# fullCURRENT_control.net
KiCad netlist of a schematic drawn in Altium Designer
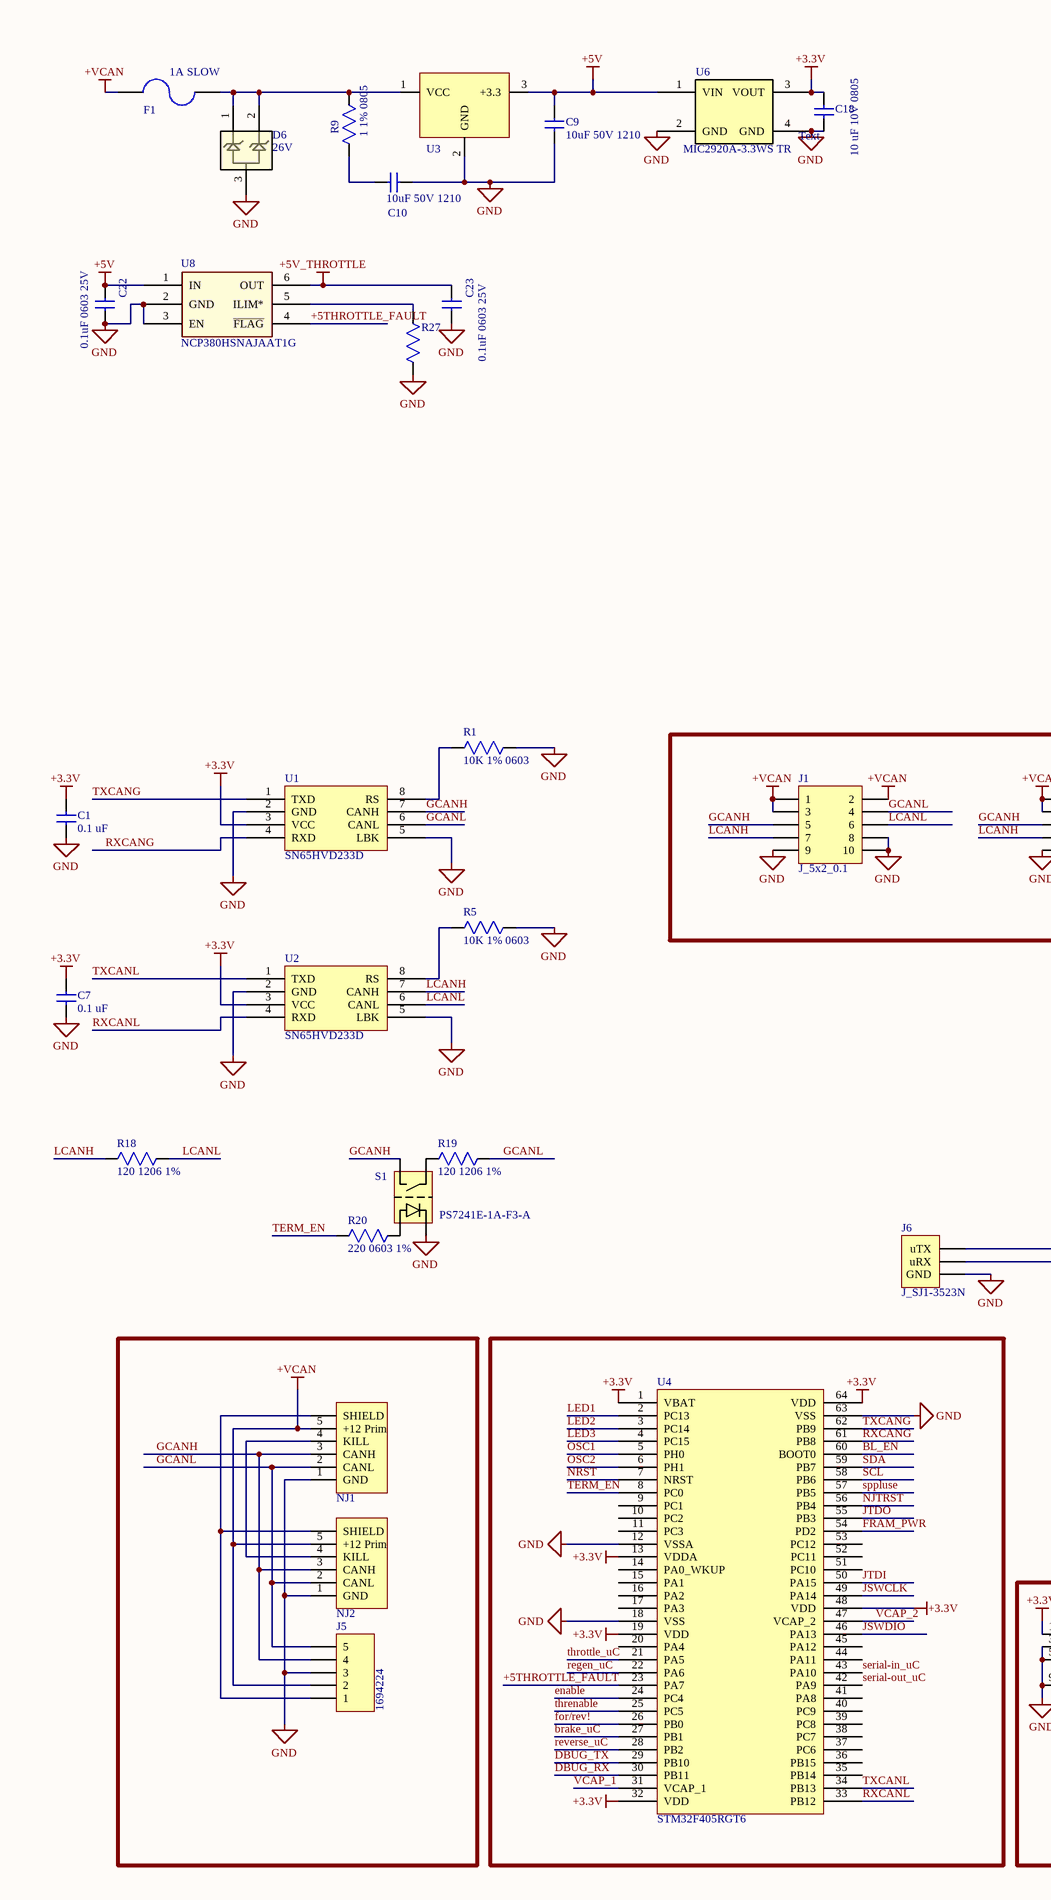
[diagram p0: fullCURRENT control.SchDoc, left]
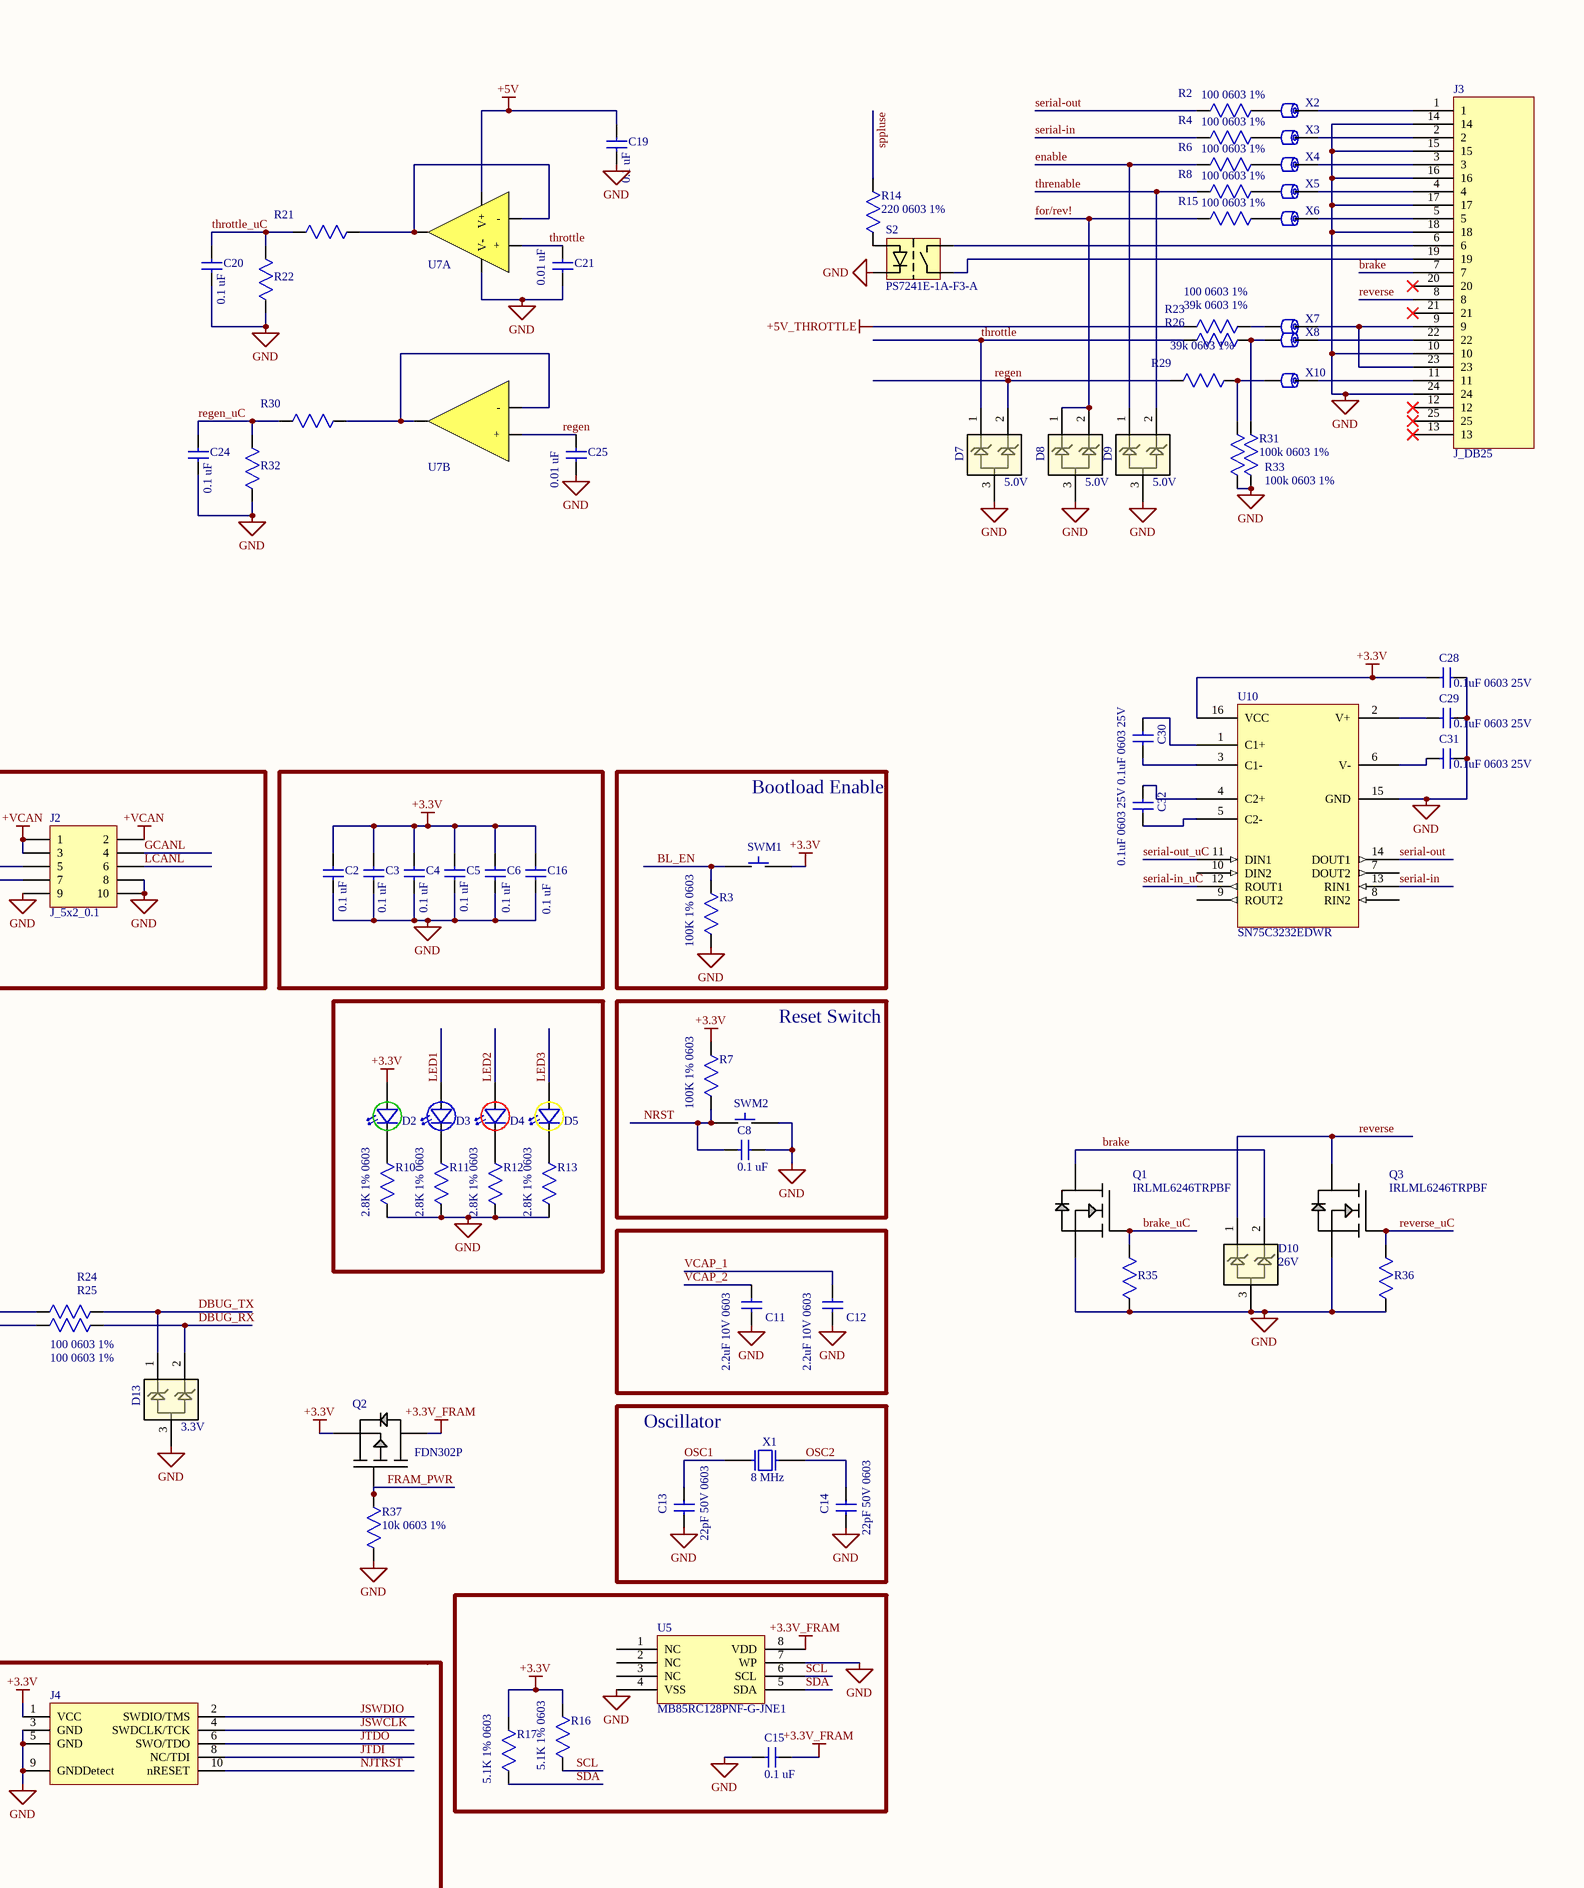
[diagram p1: fullCURRENT control.SchDoc, right]

(export (version "E")
  (design (tool "Eeschema 10.0.6"))
  (components
    (comp (ref "C1")
      (value "0.1 uF")
      (footprint "0603_cap")
      (description "CAP CERM 0.1uF 0603 X7R")
      (fields (field (name "MANUFACTURER") "Murata") (field (name "PART NUMBER") "GRM188R71E104KA01D"))
      (libsource (lib "Nutz") (part "C_0603"))
    )
    (comp (ref "C2")
      (value "0.1 uF")
      (footprint "0603_cap")
      (description "CAP CERM 0.1uF 0603 X7R")
      (fields (field (name "MANUFACTURER") "Murata") (field (name "PART NUMBER") "GRM188R71E104KA01D"))
      (libsource (lib "Nutz") (part "C_0603"))
    )
    (comp (ref "C3")
      (value "0.1 uF")
      (footprint "0603_cap")
      (description "CAP CERM 0.1uF 0603 X7R")
      (fields (field (name "MANUFACTURER") "Murata") (field (name "PART NUMBER") "GRM188R71E104KA01D"))
      (libsource (lib "Nutz") (part "C_0603"))
    )
    (comp (ref "C4")
      (value "0.1 uF")
      (footprint "0603_cap")
      (description "CAP CERM 0.1uF 0603 X7R")
      (fields (field (name "MANUFACTURER") "Murata") (field (name "PART NUMBER") "GRM188R71E104KA01D"))
      (libsource (lib "Nutz") (part "C_0603"))
    )
    (comp (ref "C5")
      (value "0.1 uF")
      (footprint "0603_cap")
      (description "CAP CERM 0.1uF 0603 X7R")
      (fields (field (name "MANUFACTURER") "Murata") (field (name "PART NUMBER") "GRM188R71E104KA01D"))
      (libsource (lib "Nutz") (part "C_0603"))
    )
    (comp (ref "C6")
      (value "0.1 uF")
      (footprint "0603_cap")
      (description "CAP CERM 0.1uF 0603 X7R")
      (fields (field (name "MANUFACTURER") "Murata") (field (name "PART NUMBER") "GRM188R71E104KA01D"))
      (libsource (lib "Nutz") (part "C_0603"))
    )
    (comp (ref "C7")
      (value "0.1 uF")
      (footprint "0603_cap")
      (description "CAP CERM 0.1uF 0603 X7R")
      (fields (field (name "MANUFACTURER") "Murata") (field (name "PART NUMBER") "GRM188R71E104KA01D"))
      (libsource (lib "Nutz") (part "C_0603"))
    )
    (comp (ref "C8")
      (value "0.1 uF")
      (footprint "0603_cap")
      (description "CAP CERM 0.1uF 0603 X7R")
      (fields (field (name "MANUFACTURER") "Murata") (field (name "PART NUMBER") "GRM188R71E104KA01D"))
      (libsource (lib "Nutz") (part "C_0603"))
    )
    (comp (ref "C9")
      (value "10uF 50V 1210")
      (footprint "1210_Capacitor")
      (description "CAP CER 10UF 50V 10% X5R 1210")
      (fields (field (name "MANUFACTURER") "Taiyo Yuden") (field (name "PART NUMBER") "UMK325AB7106MM-T"))
      (libsource (lib "d1_SchLib") (part "C_1210_10uF"))
    )
    (comp (ref "C10")
      (value "10uF 50V 1210")
      (footprint "1210_Capacitor")
      (description "CAP CER 10UF 50V 10% X5R 1210")
      (fields (field (name "MANUFACTURER") "Taiyo Yuden") (field (name "PART NUMBER") "UMK325AB7106MM-T"))
      (libsource (lib "d1_SchLib") (part "C_1210_10uF"))
    )
    (comp (ref "C11")
      (value "2.2uF 10V 0603")
      (footprint "0603_cap")
      (description "CAP CER 2.2UF 10V 10% X7R 0603")
      (fields (field (name "MANUFACTURER") "Taiyo Yuden") (field (name "PART NUMBER") "LMK107B7225KA-T"))
      (libsource (lib "Nutz") (part "C_0603"))
    )
    (comp (ref "C12")
      (value "2.2uF 10V 0603")
      (footprint "0603_cap")
      (description "CAP CER 2.2UF 10V 10% X7R 0603")
      (fields (field (name "MANUFACTURER") "Taiyo Yuden") (field (name "PART NUMBER") "LMK107B7225KA-T"))
      (libsource (lib "Nutz") (part "C_0603"))
    )
    (comp (ref "C13")
      (value "22pF 50V 0603")
      (footprint "0603_cap")
      (description "CAP CER 22PF 50V 5% NPO 0603")
      (fields (field (name "MANUFACTURER") "Yageo") (field (name "PART NUMBER") "CC0603JRNPO9BN200"))
      (libsource (lib "Nutz") (part "C_0603"))
    )
    (comp (ref "C14")
      (value "22pF 50V 0603")
      (footprint "0603_cap")
      (description "CAP CER 22PF 50V 5% NPO 0603")
      (fields (field (name "MANUFACTURER") "Yageo") (field (name "PART NUMBER") "CC0603JRNPO9BN200"))
      (libsource (lib "Nutz") (part "C_0603"))
    )
    (comp (ref "C15")
      (value "0.1 uF")
      (footprint "0603_cap")
      (description "CAP CERM 0.1uF 0603 X7R")
      (fields (field (name "MANUFACTURER") "Murata") (field (name "PART NUMBER") "GRM188R71E104KA01D"))
      (libsource (lib "Nutz") (part "C_0603"))
    )
    (comp (ref "C16")
      (value "0.1 uF")
      (footprint "0603_cap")
      (description "CAP CERM 0.1uF 0603 X7R")
      (fields (field (name "MANUFACTURER") "Murata") (field (name "PART NUMBER") "GRM188R71E104KA01D"))
      (libsource (lib "Nutz") (part "C_0603"))
    )
    (comp (ref "C18")
      (value "10 uF 10V 0805")
      (footprint "0805_Capacitor")
      (description "CAP CERM 0805")
      (fields (field (name "Comment") "CAP 0805"))
      (libsource (lib "Nutz") (part "C_0805"))
    )
    (comp (ref "C19")
      (value "0.1 uF")
      (footprint "0603_cap")
      (description "CAP CERM 0.1uF 0603 X7R")
      (fields (field (name "MANUFACTURER") "Murata") (field (name "PART NUMBER") "GRM188R71E104KA01D"))
      (libsource (lib "Nutz") (part "C_0603"))
    )
    (comp (ref "C20")
      (value "0.1 uF")
      (footprint "0603_cap")
      (description "CAP CERM 0.1uF 0603 X7R")
      (fields (field (name "MANUFACTURER") "Murata") (field (name "PART NUMBER") "GRM188R71E104KA01D"))
      (libsource (lib "Nutz") (part "C_0603"))
    )
    (comp (ref "C21")
      (value "0.01 uF")
      (footprint "0603_cap")
      (description "CAP CERM 0.01uF 0603 X7R")
      (fields (field (name "MANUFACTURER") "Murata") (field (name "Comment") "CAP 0603"))
      (libsource (lib "Nutz") (part "C_0603"))
    )
    (comp (ref "C22")
      (value "0.1uF 0603 25V")
      (footprint "0603_cap")
      (description "CAP CERM 0.1uF 0603 X7R")
      (fields (field (name "Comment") "CAP 0603"))
      (libsource (lib "Nutz") (part "C_0603"))
    )
    (comp (ref "C23")
      (value "0.1uF 0603 25V")
      (footprint "0603_cap")
      (description "CAP CERM 0.1uF 0603 X7R")
      (fields (field (name "Comment") "CAP 0603"))
      (libsource (lib "Nutz") (part "C_0603"))
    )
    (comp (ref "C24")
      (value "0.1 uF")
      (footprint "0603_cap")
      (description "CAP CERM 0.1uF 0603 X7R")
      (fields (field (name "MANUFACTURER") "Murata") (field (name "PART NUMBER") "GRM188R71E104KA01D"))
      (libsource (lib "Nutz") (part "C_0603"))
    )
    (comp (ref "C25")
      (value "0.01 uF")
      (footprint "0603_cap")
      (description "CAP CERM 0.01uF 0603 X7R")
      (fields (field (name "MANUFACTURER") "Murata") (field (name "Comment") "CAP 0603"))
      (libsource (lib "Nutz") (part "C_0603"))
    )
    (comp (ref "C28")
      (value "0.1uF 0603 25V")
      (footprint "0603_cap")
      (description "CAP CERM 0.1uF 0603 X7R")
      (fields (field (name "Comment") "CAP 0603"))
      (libsource (lib "Nutz") (part "C_0603"))
    )
    (comp (ref "C29")
      (value "0.1uF 0603 25V")
      (footprint "0603_cap")
      (description "CAP CERM 0.1uF 0603 X7R")
      (fields (field (name "Comment") "CAP 0603"))
      (libsource (lib "Nutz") (part "C_0603"))
    )
    (comp (ref "C30")
      (value "0.1uF 0603 25V")
      (footprint "0603_cap")
      (description "CAP CERM 0.1uF 0603 X7R")
      (fields (field (name "Comment") "CAP 0603"))
      (libsource (lib "Nutz") (part "C_0603"))
    )
    (comp (ref "C31")
      (value "0.1uF 0603 25V")
      (footprint "0603_cap")
      (description "CAP CERM 0.1uF 0603 X7R")
      (fields (field (name "Comment") "CAP 0603"))
      (libsource (lib "Nutz") (part "C_0603"))
    )
    (comp (ref "C32")
      (value "0.1uF 0603 25V")
      (footprint "0603_cap")
      (description "CAP CERM 0.1uF 0603 X7R")
      (fields (field (name "Comment") "CAP 0603"))
      (libsource (lib "Nutz") (part "C_0603"))
    )
    (comp (ref "D2")
      (value "3MM GREEN")
      (footprint "LED 3MM GREEN")
      (description "LED 3MM GREEN")
      (libsource (lib "Nutz") (part "D_LED 3MM GREEN"))
    )
    (comp (ref "D3")
      (value "3MM YELLOW")
      (footprint "LED 3MM BLUE")
      (description "LED 3MM BLUE")
      (libsource (lib "Nutz") (part "D_LED 3MM BLUE"))
    )
    (comp (ref "D4")
      (value "3MM RED")
      (footprint "LED 3MM RED")
      (description "LED 3MM RED")
      (libsource (lib "Nutz") (part "D_LED 3MM RED"))
    )
    (comp (ref "D5")
      (value "3MM YELLOW")
      (footprint "LED 3MM YELLOW")
      (description "LED 3MM YELLOW")
      (libsource (lib "Nutz") (part "D_LED 3MM YELLOW"))
    )
    (comp (ref "D6") (value "26V") (footprint "SOT-23") (libsource (lib "d1_SchLib") (part "D_TVS_12V")))
    (comp (ref "D7")
      (value "5.0V")
      (footprint "SOT-23")
      (description "5.0V TVS SOT23")
      (libsource (lib "Nutz") (part "D_TVS_5"))
    )
    (comp (ref "D8")
      (value "5.0V")
      (footprint "SOT-23")
      (description "5.0V TVS SOT23")
      (libsource (lib "Nutz") (part "D_TVS_5"))
    )
    (comp (ref "D9")
      (value "5.0V")
      (footprint "SOT-23")
      (description "5.0V TVS SOT23")
      (libsource (lib "Nutz") (part "D_TVS_5"))
    )
    (comp (ref "D10") (value "26V") (footprint "SOT-23") (libsource (lib "d1_SchLib") (part "D_TVS_12V")))
    (comp (ref "D13")
      (value "3.3V")
      (footprint "SOT-23")
      (description "3.3V TVS SOT23")
      (libsource (lib "Nutz") (part "D_TVS_5"))
    )
    (comp (ref "F1")
      (value "F_2410")
      (footprint "2410")
      (description "FUSE 2410")
      (fields (field (name "CURRENT RATING") "1A SLOW"))
      (libsource (lib "d1_SchLib") (part "F_2410"))
    )
    (comp (ref "J1")
      (value "J_5x2_0.1")
      (footprint "10PIN_2_.100IN")
      (description "5 x 2 0.1\" Header")
      (libsource (lib "Nutz") (part "J_5x2_0.1"))
    )
    (comp (ref "J2")
      (value "J_5x2_0.1")
      (footprint "10PIN_2_.100IN")
      (description "5 x 2 0.1\" Header")
      (libsource (lib "Nutz") (part "J_5x2_0.1"))
    )
    (comp (ref "J3") (value "J_DB25") (footprint "DB25") (libsource (lib "Nutz") (part "J_DB25")))
    (comp (ref "J4")
      (value "J_CORTEX_DEBUG")
      (footprint "CORTEX_DEBUG")
      (description "CORTEX JTAG DEBUG CONNECTOR")
      (fields (field (name "PART NUMBER") "FTSH-105-01-F-D") (field (name "MANUFACTURER") "Samtec"))
      (libsource (lib "Nutz") (part "J_CORTEX_DEBUG"))
    )
    (comp (ref "J5")
      (value "1694224")
      (footprint "WFSFDH4.5")
      (description "CONNECTOR, 5-pos., M12, A-coded")
      (fields (field (name "MANUFACTURER") "PHOENIX CONTACT/EQUIV."))
      (libsource (lib "Miscellaneous Connectors") (part "Header 5"))
    )
    (comp (ref "J6")
      (value "J_SJ1-3523N")
      (footprint "SJ1-3523N")
      (description "CONN JACK STEREO R/A 3PIN 3.5MM")
      (fields (field (name "PART NUMBER") "SJ1-3523N") (field (name "MANUFACTURER") "CUI"))
      (libsource (lib "Nutz") (part "J_SJ1-3523N"))
    )
    (comp (ref "NJ1")
      (value "NC5FBH_D1")
      (footprint "NC5FBH")
      (description "D1 Bus Connector")
      (fields (field (name "MANUFACTURER") "Neutrik") (field (name "PART NUMBER") "NC5FBH"))
      (libsource (lib "neutrik") (part "NC5FBH_D1"))
    )
    (comp (ref "NJ2")
      (value "NC5MBH_D1")
      (footprint "NC5MBH")
      (description "D1 Bus Connector")
      (fields (field (name "MANUFACTURER") "Neutrik") (field (name "PART NUMBER") "NC5MBH"))
      (libsource (lib "neutrik") (part "NC5MBH_D1"))
    )
    (comp (ref "Q1")
      (value "Q_IRLML6246TRPBF")
      (footprint "SOT-23")
      (description "MOSFET N-CH 20V 4.1A SOT-23")
      (fields (field (name "MANUFACTURER") "Alpha & Omega") (field (name "PART NUMBER") "IRLML6246TRPBF"))
      (libsource (lib "Nutz") (part "Q_IRLML6246TRPBF"))
    )
    (comp (ref "Q2")
      (value "FDN302P")
      (footprint "SOT-23")
      (description "MOSFET P-CH 20V 2.4A SSOT3")
      (fields
        (field (name "MANUFACTURER") "Fairchild Semiconductor")
        (field (name "SVP CREATOR") "Adam Shea")
        (field (name "SVP REVIEWER 1") "Nate Bolyard")
        (field (name "SVP REVIEWER 2") "Trevtron")
      )
      (libsource (lib "d1_SchLib") (part "Q_FDN302P"))
    )
    (comp (ref "Q3")
      (value "Q_IRLML6246TRPBF")
      (footprint "SOT-23")
      (description "MOSFET N-CH 20V 4.1A SOT-23")
      (fields (field (name "MANUFACTURER") "Alpha & Omega") (field (name "PART NUMBER") "IRLML6246TRPBF"))
      (libsource (lib "Nutz") (part "Q_IRLML6246TRPBF"))
    )
    (comp (ref "R1")
      (value "10K 1% 0603")
      (footprint "0603_res")
      (description "RES 10K 1% 0603")
      (fields (field (name "Comment") "RES 0603"))
      (libsource (lib "Nutz") (part "R_0603"))
    )
    (comp (ref "R2")
      (value "100 0603 1%")
      (footprint "0603_res")
      (description "RES 100 0603 1%")
      (fields (field (name "Comment") "RES 0603"))
      (libsource (lib "Nutz") (part "R_0603"))
    )
    (comp (ref "R3")
      (value "100K 1% 0603")
      (footprint "0603_res")
      (description "RES 100K 1% 0603")
      (fields (field (name "Comment") "RES 0603"))
      (libsource (lib "Nutz") (part "R_0603"))
    )
    (comp (ref "R4")
      (value "100 0603 1%")
      (footprint "0603_res")
      (description "RES 100 0603 1%")
      (fields (field (name "Comment") "RES 0603"))
      (libsource (lib "Nutz") (part "R_0603"))
    )
    (comp (ref "R5")
      (value "10K 1% 0603")
      (footprint "0603_res")
      (description "RES 10K 1% 0603")
      (fields (field (name "Comment") "RES 0603"))
      (libsource (lib "Nutz") (part "R_0603"))
    )
    (comp (ref "R6")
      (value "100 0603 1%")
      (footprint "0603_res")
      (description "RES 100 0603 1%")
      (fields (field (name "Comment") "RES 0603"))
      (libsource (lib "Nutz") (part "R_0603"))
    )
    (comp (ref "R7")
      (value "100K 1% 0603")
      (footprint "0603_res")
      (description "RES 100K 1% 0603")
      (fields (field (name "Comment") "RES 0603"))
      (libsource (lib "Nutz") (part "R_0603"))
    )
    (comp (ref "R8")
      (value "100 0603 1%")
      (footprint "0603_res")
      (description "RES 100 0603 1%")
      (fields (field (name "Comment") "RES 0603"))
      (libsource (lib "Nutz") (part "R_0603"))
    )
    (comp (ref "R9")
      (value "1 1% 0805")
      (footprint "0805_Resistor")
      (description "RES 1 OHM 1/8W 1% 0805 SMD")
      (fields (field (name "Comment") "R_0805_1_1%"))
      (libsource (lib "d1_SchLib") (part "R_0805_1_1%"))
    )
    (comp (ref "R10")
      (value "2.8K 1% 0603")
      (footprint "0603_res")
      (description "RES 300 1% 0603")
      (fields (field (name "Comment") "RES 0603"))
      (libsource (lib "Nutz") (part "R_0603"))
    )
    (comp (ref "R11")
      (value "2.8K 1% 0603")
      (footprint "0603_res")
      (description "RES 300 1% 0603")
      (fields (field (name "Comment") "RES 0603"))
      (libsource (lib "Nutz") (part "R_0603"))
    )
    (comp (ref "R12")
      (value "2.8K 1% 0603")
      (footprint "0603_res")
      (description "RES 300 1% 0603")
      (fields (field (name "Comment") "RES 0603"))
      (libsource (lib "Nutz") (part "R_0603"))
    )
    (comp (ref "R13")
      (value "2.8K 1% 0603")
      (footprint "0603_res")
      (description "RES 300 1% 0603")
      (fields (field (name "Comment") "RES 0603"))
      (libsource (lib "Nutz") (part "R_0603"))
    )
    (comp (ref "R14")
      (value "220 0603 1%")
      (footprint "0603_res")
      (description "RES 220 0603 1%")
      (fields (field (name "MANUFACTURER") "Yageo") (field (name "PART NUMBER") "RC0603FR-07220RL"))
      (libsource (lib "Nutz") (part "R_0603"))
    )
    (comp (ref "R15")
      (value "100 0603 1%")
      (footprint "0603_res")
      (description "RES 100 0603 1%")
      (fields (field (name "Comment") "RES 0603"))
      (libsource (lib "Nutz") (part "R_0603"))
    )
    (comp (ref "R16")
      (value "5.1K 1% 0603")
      (footprint "0603_res")
      (description "RES 5.1K 1% 0603")
      (fields (field (name "Comment") "RES 0603"))
      (libsource (lib "Nutz") (part "R_0603"))
    )
    (comp (ref "R17")
      (value "5.1K 1% 0603")
      (footprint "0603_res")
      (description "RES 5.1K 1% 0603")
      (fields (field (name "Comment") "RES 0603"))
      (libsource (lib "Nutz") (part "R_0603"))
    )
    (comp (ref "R18")
      (value "120 1206 1%")
      (footprint "1206_Resistor")
      (description "RES 120 1206 1%")
      (fields (field (name "Comment") "RES 1206"))
      (libsource (lib "Nutz") (part "R_1206"))
    )
    (comp (ref "R19")
      (value "120 1206 1%")
      (footprint "1206_Resistor")
      (description "RES 120 1206 1%")
      (fields (field (name "Comment") "RES 1206"))
      (libsource (lib "Nutz") (part "R_1206"))
    )
    (comp (ref "R20")
      (value "220 0603 1%")
      (footprint "0603_res")
      (description "RES 220 0603 1%")
      (fields (field (name "MANUFACTURER") "Yageo") (field (name "PART NUMBER") "RC0603FR-07220RL"))
      (libsource (lib "Nutz") (part "R_0603"))
    )
    (comp (ref "R21") (value "RES 0603") (footprint "0603_res") (libsource (lib "Nutz") (part "R_0603")))
    (comp (ref "R22") (value "RES 0603") (footprint "0603_res") (libsource (lib "Nutz") (part "R_0603")))
    (comp (ref "R23")
      (value "100 0603 1%")
      (footprint "0603_res")
      (description "RES 100 0603 1%")
      (fields (field (name "Comment") "RES 0603"))
      (libsource (lib "Nutz") (part "R_0603"))
    )
    (comp (ref "R24")
      (value "100 0603 1%")
      (footprint "0603_res")
      (description "RES 100 0603 1%")
      (fields (field (name "Comment") "RES 0603"))
      (libsource (lib "Nutz") (part "R_0603"))
    )
    (comp (ref "R25")
      (value "100 0603 1%")
      (footprint "0603_res")
      (description "RES 100 0603 1%")
      (fields (field (name "Comment") "RES 0603"))
      (libsource (lib "Nutz") (part "R_0603"))
    )
    (comp (ref "R26")
      (value "39k 0603 1%")
      (footprint "0603_res")
      (description "RES 100 0603 1%")
      (fields (field (name "Comment") "RES 0603"))
      (libsource (lib "Nutz") (part "R_0603"))
    )
    (comp (ref "R27") (value "RES 0603") (footprint "0603_res") (libsource (lib "Nutz") (part "R_0603")))
    (comp (ref "R29")
      (value "39k 0603 1%")
      (footprint "0603_res")
      (description "RES 100 0603 1%")
      (fields (field (name "Comment") "RES 0603"))
      (libsource (lib "Nutz") (part "R_0603"))
    )
    (comp (ref "R30") (value "RES 0603") (footprint "0603_res") (libsource (lib "Nutz") (part "R_0603")))
    (comp (ref "R31")
      (value "100k 0603 1%")
      (footprint "0603_res")
      (description "RES 100k 0603 1%")
      (fields (field (name "Comment") "RES 0603"))
      (libsource (lib "Nutz") (part "R_0603"))
    )
    (comp (ref "R32") (value "RES 0603") (footprint "0603_res") (libsource (lib "Nutz") (part "R_0603")))
    (comp (ref "R33")
      (value "100k 0603 1%")
      (footprint "0603_res")
      (description "RES 100k 0603 1%")
      (fields (field (name "Comment") "RES 0603"))
      (libsource (lib "Nutz") (part "R_0603"))
    )
    (comp (ref "R35") (value "RES 0603") (footprint "0603_res") (libsource (lib "Nutz") (part "R_0603")))
    (comp (ref "R36") (value "RES 0603") (footprint "0603_res") (libsource (lib "Nutz") (part "R_0603")))
    (comp (ref "R37")
      (value "10k 0603 1%")
      (footprint "0603_res")
      (description "RES 10K 0603 1%")
      (fields (field (name "Comment") "RES 0603"))
      (libsource (lib "Nutz") (part "R_0603"))
    )
    (comp (ref "S1")
      (value "S_PS7241E-1A-F3-A")
      (footprint "4SOP-GULL")
      (description "SSR OCMOS FET 120MA 1CH NO 4-SOP")
      (fields (field (name "MANUFACTURER") "CEL") (field (name "PART NUMBER") "PS7241E-1A-F3-A"))
      (libsource (lib "Nutz") (part "S_PS7241E-1A-F3-A"))
    )
    (comp (ref "S2")
      (value "S_PS7241E-1A-F3-A")
      (footprint "4SOP-GULL")
      (description "SSR OCMOS FET 120MA 1CH NO 4-SOP")
      (fields (field (name "MANUFACTURER") "CEL") (field (name "PART NUMBER") "PS7241E-1A-F3-A"))
      (libsource (lib "") (part "S_PS7241E-1A-F3-A_1"))
    )
    (comp (ref "SWM1")
      (value "SW_TACT_SWITCH_6x6")
      (footprint "TACT_SWITCH_6x6")
      (description "SWITCH TACTILE SPST-NO 0.05A 12V")
      (fields (field (name "MANUFACTURER") "C&K Components") (field (name "PART NUMBER") "PTS645SK43 LFS"))
      (libsource (lib "d1_SchLib") (part "SW_TACT_SWITCH_6x6"))
    )
    (comp (ref "SWM2")
      (value "SW_TACT_SWITCH_6x6")
      (footprint "TACT_SWITCH_6x6")
      (description "SWITCH TACTILE SPST-NO 0.05A 12V")
      (fields (field (name "MANUFACTURER") "C&K Components") (field (name "PART NUMBER") "PTS645SK43 LFS"))
      (libsource (lib "d1_SchLib") (part "SW_TACT_SWITCH_6x6"))
    )
    (comp (ref "U1")
      (value "U_SN65HVD233D")
      (footprint "SOIC127P600X175-8N")
      (description "IC 3.3V CAN TXRX 8-SOIC")
      (fields (field (name "MANUFACTURER") "Texas Instruments") (field (name "PART NUMBER") "SN65HVD233D"))
      (libsource (lib "Nutz") (part "U_SN65HVD233D"))
    )
    (comp (ref "U2")
      (value "U_SN65HVD233D")
      (footprint "SOIC127P600X175-8N")
      (description "IC 3.3V CAN TXRX 8-SOIC")
      (fields (field (name "MANUFACTURER") "Texas Instruments") (field (name "PART NUMBER") "SN65HVD233D"))
      (libsource (lib "Nutz") (part "U_SN65HVD233D"))
    )
    (comp (ref "U3")
      (value "R-783.3-0.5")
      (footprint "SIP3")
      (description "IC REG 0.5A 3.3V")
      (fields (field (name "MANUFACTURER") "Recom Power"))
      (libsource (lib "Vivs") (part "U_R-783.3-0.5"))
    )
    (comp (ref "U4")
      (value "STM32F405RGT6")
      (footprint "STM32_LQFP64")
      (description "IC MCU 32BIT 1MB FLASH 64LQFP")
      (fields (field (name "MANUFACTURER") "STMicroelectronics"))
      (libsource (lib "Nutz") (part "U_STM32F405RGT6"))
    )
    (comp (ref "U5")
      (value "MB85RC128PNF-G-JNE1")
      (footprint "SOIC127P600X175-8N")
      (description "IC FRAM 128KBIT 400KHZ 8SOP")
      (fields
        (field (name "MANUFACTURER") "Fujitsu Semiconductor America Inc")
        (field (name "PART NUMBER") "MB85RC128PNF-G-JNE1")
      )
      (libsource (lib "c3_SchLib") (part "U_MB85RC16PNF-G-JNE1"))
    )
    (comp (ref "U6")
      (value "U_MIC2920A-3.3WS")
      (footprint "SOT-223")
      (description "IC REG LDO 3.3V .4A SOT223")
      (fields (field (name "MANUFACTURER") "Mircrel") (field (name "PART NUMBER") "MIC2920A-3.3WS TR"))
      (libsource (lib "Nutz") (part "U_MIC2920A-3.3WS"))
    )
    (comp (ref "U7")
      (value "IC OP AMP")
      (footprint "SOIC127P600X175-8N")
      (description "IC OPAMP 1UA 1.4V DUAL R-R 8SOIC")
      (fields (field (name "MANUFACTURER") "Microchip") (field (name "SVP CREATOR") "Jonathan Nutzmann"))
      (libsource (lib "d1_SchLib") (part "U_MCP6042T-I/SN"))
    )
    (comp (ref "U8")
      (value "NCP380HSNAJAAT1G")
      (footprint "tsop-6")
      (description "IC CURRENT LIMIT SWITCH 6-TSOP")
      (fields
        (field (name "MANUFACTURER") "ON Semiconductor")
        (field (name "PART NUMBER") "NCP380HSNAJAAT1G")
      )
      (libsource (lib "Nutz") (part "U_NCP380HSNAJAAT1G"))
    )
    (comp (ref "U10")
      (value "SN75C3232EDWR")
      (footprint "SOIC127P600X175-16N")
      (description "IC LINE DRVR/RCVR RS232 16-SOIC")
      (fields
        (field (name "MANUFACTURER") "TI")
        (field (name "Comment") "U_SN75C3232EDWR")
        (field (name "SVP CREATOR") "Jonathan Nutzmann")
      )
      (libsource (lib "c3_SchLib") (part "U_SN75C3232EDWR"))
    )
    (comp (ref "X1")
      (value "8 MHz")
      (footprint "HC-49")
      (description "CRYSTAL 8.0 MHZ 20PF")
      (fields (field (name "PART NUMBER") "FOXSLF/080-20") (field (name "MANUFACTURER") "Fox Electronics"))
      (libsource (lib "d1_SchLib") (part "X_HC49"))
    )
    (comp (ref "X2")
      (value "0603")
      (footprint "0603_res")
      (description "FERRITE 0603")
      (libsource (lib "Nutz") (part "X_0603_FERRITE"))
    )
    (comp (ref "X3")
      (value "0603")
      (footprint "0603_res")
      (description "FERRITE 0603")
      (libsource (lib "Nutz") (part "X_0603_FERRITE"))
    )
    (comp (ref "X4")
      (value "0603")
      (footprint "0603_res")
      (description "FERRITE 0603")
      (libsource (lib "Nutz") (part "X_0603_FERRITE"))
    )
    (comp (ref "X5")
      (value "0603")
      (footprint "0603_res")
      (description "FERRITE 0603")
      (libsource (lib "Nutz") (part "X_0603_FERRITE"))
    )
    (comp (ref "X6")
      (value "0603")
      (footprint "0603_res")
      (description "FERRITE 0603")
      (libsource (lib "Nutz") (part "X_0603_FERRITE"))
    )
    (comp (ref "X7")
      (value "0603")
      (footprint "0603_res")
      (description "FERRITE 0603")
      (libsource (lib "Nutz") (part "X_0603_FERRITE"))
    )
    (comp (ref "X8")
      (value "0603")
      (footprint "0603_res")
      (description "FERRITE 0603")
      (libsource (lib "Nutz") (part "X_0603_FERRITE"))
    )
    (comp (ref "X10")
      (value "0603")
      (footprint "0603_res")
      (description "FERRITE 0603")
      (libsource (lib "Nutz") (part "X_0603_FERRITE"))
    )
  )
  (nets
    (net (code "1") (name "+3.3V") (class "Default")
      (node (ref "C1") (pin "1") (pinfunction "1_1") (pintype "passive"))
      (node (ref "C16") (pin "1") (pinfunction "1_1") (pintype "passive"))
      (node (ref "C18") (pin "2") (pinfunction "2_2") (pintype "passive"))
      (node (ref "C2") (pin "1") (pinfunction "1_1") (pintype "passive"))
      (node (ref "C28") (pin "1") (pinfunction "1_1") (pintype "passive"))
      (node (ref "C3") (pin "1") (pinfunction "1_1") (pintype "passive"))
      (node (ref "C4") (pin "1") (pinfunction "1_1") (pintype "passive"))
      (node (ref "C5") (pin "1") (pinfunction "1_1") (pintype "passive"))
      (node (ref "C6") (pin "1") (pinfunction "1_1") (pintype "passive"))
      (node (ref "C7") (pin "1") (pinfunction "1_1") (pintype "passive"))
      (node (ref "D2") (pin "A") (pinfunction "Anode_A") (pintype "passive"))
      (node (ref "J4") (pin "1") (pinfunction "VCC_1") (pintype "passive"))
      (node (ref "Q2") (pin "2") (pinfunction "SOURCE_2") (pintype "passive"))
      (node (ref "R16") (pin "1") (pinfunction "1_1") (pintype "passive"))
      (node (ref "R17") (pin "1") (pinfunction "1_1") (pintype "passive"))
      (node (ref "R7") (pin "1") (pinfunction "1_1") (pintype "passive"))
      (node (ref "SWM1") (pin "2") (pinfunction "2_2") (pintype "passive"))
      (node (ref "U1") (pin "3") (pinfunction "VCC_3") (pintype "passive"))
      (node (ref "U10") (pin "16") (pinfunction "VCC_16") (pintype "passive"))
      (node (ref "U2") (pin "3") (pinfunction "VCC_3") (pintype "passive"))
      (node (ref "U4") (pin "1") (pinfunction "VBAT_1") (pintype "passive"))
      (node (ref "U4") (pin "13") (pinfunction "VDDA_13") (pintype "passive"))
      (node (ref "U4") (pin "19") (pinfunction "VDD_19") (pintype "passive"))
      (node (ref "U4") (pin "32") (pinfunction "VDD_32") (pintype "passive"))
      (node (ref "U4") (pin "48") (pinfunction "VDD_48") (pintype "passive"))
      (node (ref "U4") (pin "64") (pinfunction "VDD_64") (pintype "passive"))
      (node (ref "U6") (pin "3") (pinfunction "VOUT_3") (pintype "passive"))
    )
    (net (code "2") (name "+3.3V_FRAM") (class "Default")
      (node (ref "C15") (pin "2") (pinfunction "2_2") (pintype "passive"))
      (node (ref "Q2") (pin "3") (pinfunction "DRAIN_3") (pintype "passive"))
      (node (ref "U5") (pin "8") (pinfunction "VDD_8") (pintype "passive"))
    )
    (net (code "3") (name "+5V") (class "Default")
      (node (ref "C19") (pin "1") (pinfunction "1_1") (pintype "passive"))
      (node (ref "C22") (pin "2") (pinfunction "2_2") (pintype "passive"))
      (node (ref "C9") (pin "2") (pinfunction "2_2") (pintype "passive"))
      (node (ref "U3") (pin "3") (pinfunction "+3.3_3") (pintype "passive"))
      (node (ref "U6") (pin "1") (pinfunction "VIN_1") (pintype "passive"))
      (node (ref "U7") (pin "8") (pinfunction "V+_8") (pintype "passive"))
      (node (ref "U8") (pin "1") (pinfunction "IN_1") (pintype "passive"))
    )
    (net (code "4") (name "+5V_THROTTLE") (class "Default")
      (node (ref "C23") (pin "2") (pinfunction "2_2") (pintype "passive"))
      (node (ref "R23") (pin "2") (pinfunction "2_2") (pintype "passive"))
      (node (ref "U8") (pin "6") (pinfunction "OUT_6") (pintype "passive"))
    )
    (net (code "5") (name "+VCAN") (class "Default")
      (node (ref "F1") (pin "1") (pinfunction "1_1") (pintype "passive"))
      (node (ref "J1") (pin "1") (pinfunction "1_1") (pintype "passive"))
      (node (ref "J1") (pin "2") (pinfunction "2_2") (pintype "passive"))
      (node (ref "J1") (pin "3") (pinfunction "3_3") (pintype "passive"))
      (node (ref "J2") (pin "1") (pinfunction "1_1") (pintype "passive"))
      (node (ref "J2") (pin "2") (pinfunction "2_2") (pintype "passive"))
      (node (ref "J2") (pin "3") (pinfunction "3_3") (pintype "passive"))
      (node (ref "J5") (pin "2") (pinfunction "2_2") (pintype "passive"))
      (node (ref "NJ1") (pin "5") (pinfunction "+12_Prim_5") (pintype "passive"))
      (node (ref "NJ2") (pin "5") (pinfunction "+12_Prim_5") (pintype "passive"))
    )
    (net (code "6") (name "/+5THROTTLE_FAULT") (class "Default")
      (node (ref "U4") (pin "23") (pinfunction "PA7_23") (pintype "passive"))
      (node (ref "U8") (pin "4") (pinfunction "~{FLAG}_4") (pintype "passive"))
    )
    (net (code "7") (name "/BL_EN") (class "Default")
      (node (ref "R3") (pin "1") (pinfunction "1_1") (pintype "passive"))
      (node (ref "SWM1") (pin "1") (pinfunction "1_1") (pintype "passive"))
      (node (ref "U4") (pin "60") (pinfunction "BOOT0_60") (pintype "passive"))
    )
    (net (code "8") (name "/DBUG_RX") (class "Default")
      (node (ref "D13") (pin "2") (pinfunction "2_2") (pintype "passive"))
      (node (ref "R25") (pin "2") (pinfunction "2_2") (pintype "passive"))
      (node (ref "U4") (pin "30") (pinfunction "PB11_30") (pintype "passive"))
    )
    (net (code "9") (name "/DBUG_TX") (class "Default")
      (node (ref "D13") (pin "1") (pinfunction "1_1") (pintype "passive"))
      (node (ref "R24") (pin "2") (pinfunction "2_2") (pintype "passive"))
      (node (ref "U4") (pin "29") (pinfunction "PB10_29") (pintype "passive"))
    )
    (net (code "10") (name "/FRAM_PWR") (class "Default")
      (node (ref "Q2") (pin "1") (pinfunction "GATE_1") (pintype "passive"))
      (node (ref "R37") (pin "1") (pinfunction "1_1") (pintype "passive"))
      (node (ref "U4") (pin "54") (pinfunction "PD2_54") (pintype "passive"))
    )
    (net (code "11") (name "/GCANH") (class "Default")
      (node (ref "J1") (pin "5") (pinfunction "5_5") (pintype "passive"))
      (node (ref "J2") (pin "5") (pinfunction "5_5") (pintype "passive"))
      (node (ref "J5") (pin "4") (pinfunction "4_4") (pintype "passive"))
      (node (ref "NJ1") (pin "3") (pinfunction "CANH_3") (pintype "passive"))
      (node (ref "NJ2") (pin "3") (pinfunction "CANH_3") (pintype "passive"))
      (node (ref "S1") (pin "4") (pinfunction "4_4") (pintype "passive"))
      (node (ref "U1") (pin "7") (pinfunction "CANH_7") (pintype "passive"))
    )
    (net (code "12") (name "/GCANL") (class "Default")
      (node (ref "J1") (pin "4") (pinfunction "4_4") (pintype "passive"))
      (node (ref "J2") (pin "4") (pinfunction "4_4") (pintype "passive"))
      (node (ref "J5") (pin "5") (pinfunction "5_5") (pintype "passive"))
      (node (ref "NJ1") (pin "2") (pinfunction "CANL_2") (pintype "passive"))
      (node (ref "NJ2") (pin "2") (pinfunction "CANL_2") (pintype "passive"))
      (node (ref "R19") (pin "2") (pinfunction "2_2") (pintype "passive"))
      (node (ref "U1") (pin "6") (pinfunction "CANL_6") (pintype "passive"))
    )
    (net (code "13") (name "/JSWCLK") (class "Default")
      (node (ref "J4") (pin "4") (pinfunction "SWDCLK/TCK_4") (pintype "passive"))
      (node (ref "U4") (pin "49") (pinfunction "PA14_49") (pintype "passive"))
    )
    (net (code "14") (name "/JSWDIO") (class "Default")
      (node (ref "J4") (pin "2") (pinfunction "SWDIO/TMS_2") (pintype "passive"))
      (node (ref "U4") (pin "46") (pinfunction "PA13_46") (pintype "passive"))
    )
    (net (code "15") (name "/JTDI") (class "Default")
      (node (ref "J4") (pin "8") (pinfunction "NC/TDI_8") (pintype "passive"))
      (node (ref "U4") (pin "50") (pinfunction "PA15_50") (pintype "passive"))
    )
    (net (code "16") (name "/JTDO") (class "Default")
      (node (ref "J4") (pin "6") (pinfunction "SWO/TDO_6") (pintype "passive"))
      (node (ref "U4") (pin "55") (pinfunction "PB3_55") (pintype "passive"))
    )
    (net (code "17") (name "/LCANH") (class "Default")
      (node (ref "J1") (pin "7") (pinfunction "7_7") (pintype "passive"))
      (node (ref "J2") (pin "7") (pinfunction "7_7") (pintype "passive"))
      (node (ref "R18") (pin "1") (pinfunction "1_1") (pintype "passive"))
      (node (ref "U2") (pin "7") (pinfunction "CANH_7") (pintype "passive"))
    )
    (net (code "18") (name "/LCANL") (class "Default")
      (node (ref "J1") (pin "6") (pinfunction "6_6") (pintype "passive"))
      (node (ref "J2") (pin "6") (pinfunction "6_6") (pintype "passive"))
      (node (ref "R18") (pin "2") (pinfunction "2_2") (pintype "passive"))
      (node (ref "U2") (pin "6") (pinfunction "CANL_6") (pintype "passive"))
    )
    (net (code "19") (name "/LED1") (class "Default")
      (node (ref "D3") (pin "A") (pinfunction "Anode_A") (pintype "passive"))
      (node (ref "U4") (pin "2") (pinfunction "PC13_2") (pintype "passive"))
    )
    (net (code "20") (name "/LED2") (class "Default")
      (node (ref "D4") (pin "A") (pinfunction "Anode_A") (pintype "passive"))
      (node (ref "U4") (pin "3") (pinfunction "PC14_3") (pintype "passive"))
    )
    (net (code "21") (name "/LED3") (class "Default")
      (node (ref "D5") (pin "A") (pinfunction "Anode_A") (pintype "passive"))
      (node (ref "U4") (pin "4") (pinfunction "PC15_4") (pintype "passive"))
    )
    (net (code "22") (name "/NJTRST") (class "Default")
      (node (ref "J4") (pin "10") (pinfunction "nRESET_10") (pintype "passive"))
      (node (ref "U4") (pin "56") (pinfunction "PB4_56") (pintype "passive"))
    )
    (net (code "23") (name "/NRST") (class "Default")
      (node (ref "C8") (pin "2") (pinfunction "2_2") (pintype "passive"))
      (node (ref "R7") (pin "2") (pinfunction "2_2") (pintype "passive"))
      (node (ref "SWM2") (pin "1") (pinfunction "1_1") (pintype "passive"))
      (node (ref "U4") (pin "7") (pinfunction "NRST_7") (pintype "passive"))
    )
    (net (code "24") (name "/OSC1") (class "Default")
      (node (ref "C13") (pin "1") (pinfunction "1_1") (pintype "passive"))
      (node (ref "U4") (pin "5") (pinfunction "PH0_5") (pintype "passive"))
      (node (ref "X1") (pin "1") (pinfunction "1_1") (pintype "passive"))
    )
    (net (code "25") (name "/OSC2") (class "Default")
      (node (ref "C14") (pin "1") (pinfunction "1_1") (pintype "passive"))
      (node (ref "U4") (pin "6") (pinfunction "PH1_6") (pintype "passive"))
      (node (ref "X1") (pin "2") (pinfunction "2_2") (pintype "passive"))
    )
    (net (code "26") (name "/RXCANG") (class "Default")
      (node (ref "U1") (pin "4") (pinfunction "RXD_4") (pintype "passive"))
      (node (ref "U4") (pin "61") (pinfunction "PB8_61") (pintype "passive"))
    )
    (net (code "27") (name "/RXCANL") (class "Default")
      (node (ref "U2") (pin "4") (pinfunction "RXD_4") (pintype "passive"))
      (node (ref "U4") (pin "33") (pinfunction "PB12_33") (pintype "passive"))
    )
    (net (code "28") (name "/SCL") (class "Default")
      (node (ref "R16") (pin "2") (pinfunction "2_2") (pintype "passive"))
      (node (ref "U4") (pin "58") (pinfunction "PB6_58") (pintype "passive"))
      (node (ref "U5") (pin "6") (pinfunction "SCL_6") (pintype "passive"))
    )
    (net (code "29") (name "/SDA") (class "Default")
      (node (ref "R17") (pin "2") (pinfunction "2_2") (pintype "passive"))
      (node (ref "U4") (pin "59") (pinfunction "PB7_59") (pintype "passive"))
      (node (ref "U5") (pin "5") (pinfunction "SDA_5") (pintype "passive"))
    )
    (net (code "30") (name "/TERM_EN") (class "Default")
      (node (ref "R20") (pin "2") (pinfunction "2_2") (pintype "passive"))
      (node (ref "U4") (pin "8") (pinfunction "PC0_8") (pintype "passive"))
    )
    (net (code "31") (name "/TXCANG") (class "Default")
      (node (ref "U1") (pin "1") (pinfunction "TXD_1") (pintype "passive"))
      (node (ref "U4") (pin "62") (pinfunction "PB9_62") (pintype "passive"))
    )
    (net (code "32") (name "/TXCANL") (class "Default")
      (node (ref "U2") (pin "1") (pinfunction "TXD_1") (pintype "passive"))
      (node (ref "U4") (pin "34") (pinfunction "PB13_34") (pintype "passive"))
    )
    (net (code "33") (name "/VCAP_1") (class "Default")
      (node (ref "C12") (pin "1") (pinfunction "1_1") (pintype "passive"))
      (node (ref "U4") (pin "31") (pinfunction "VCAP_1_31") (pintype "passive"))
    )
    (net (code "34") (name "/VCAP_2") (class "Default")
      (node (ref "C11") (pin "1") (pinfunction "1_1") (pintype "passive"))
      (node (ref "U4") (pin "47") (pinfunction "VCAP_2_47") (pintype "passive"))
    )
    (net (code "35") (name "/brake") (class "Default")
      (node (ref "D10") (pin "2") (pinfunction "2_2") (pintype "passive"))
      (node (ref "J3") (pin "7") (pinfunction "7_7") (pintype "passive"))
      (node (ref "Q1") (pin "3") (pinfunction "DRAIN_3") (pintype "passive"))
    )
    (net (code "36") (name "/brake_uC") (class "Default")
      (node (ref "Q1") (pin "1") (pinfunction "GATE_1") (pintype "passive"))
      (node (ref "R35") (pin "2") (pinfunction "2_2") (pintype "passive"))
      (node (ref "U4") (pin "27") (pinfunction "PB1_27") (pintype "passive"))
    )
    (net (code "37") (name "/enable") (class "Default")
      (node (ref "D9") (pin "1") (pinfunction "1_1") (pintype "passive"))
      (node (ref "R6") (pin "2") (pinfunction "2_2") (pintype "passive"))
      (node (ref "U4") (pin "24") (pinfunction "PC4_24") (pintype "passive"))
    )
    (net (code "38") (name "/for{slash}rev!") (class "Default")
      (node (ref "D8") (pin "1") (pinfunction "1_1") (pintype "passive"))
      (node (ref "D8") (pin "2") (pinfunction "2_2") (pintype "passive"))
      (node (ref "R15") (pin "2") (pinfunction "2_2") (pintype "passive"))
      (node (ref "U4") (pin "26") (pinfunction "PB0_26") (pintype "passive"))
    )
    (net (code "39") (name "/regen") (class "Default")
      (node (ref "C25") (pin "1") (pinfunction "1_1") (pintype "passive"))
      (node (ref "D7") (pin "2") (pinfunction "2_2") (pintype "passive"))
      (node (ref "R29") (pin "2") (pinfunction "2_2") (pintype "passive"))
      (node (ref "U7") (pin "5") (pinfunction "+_5") (pintype "passive"))
    )
    (net (code "40") (name "/regen_uC") (class "Default")
      (node (ref "C24") (pin "1") (pinfunction "1_1") (pintype "passive"))
      (node (ref "R30") (pin "2") (pinfunction "2_2") (pintype "passive"))
      (node (ref "R32") (pin "2") (pinfunction "2_2") (pintype "passive"))
      (node (ref "U4") (pin "22") (pinfunction "PA6_22") (pintype "passive"))
    )
    (net (code "41") (name "/reverse") (class "Default")
      (node (ref "D10") (pin "1") (pinfunction "1_1") (pintype "passive"))
      (node (ref "J3") (pin "8") (pinfunction "8_8") (pintype "passive"))
      (node (ref "Q3") (pin "3") (pinfunction "DRAIN_3") (pintype "passive"))
    )
    (net (code "42") (name "/reverse_uC") (class "Default")
      (node (ref "Q3") (pin "1") (pinfunction "GATE_1") (pintype "passive"))
      (node (ref "R36") (pin "2") (pinfunction "2_2") (pintype "passive"))
      (node (ref "U4") (pin "28") (pinfunction "PB2_28") (pintype "passive"))
    )
    (net (code "43") (name "/serial-in") (class "Default")
      (node (ref "R4") (pin "2") (pinfunction "2_2") (pintype "passive"))
      (node (ref "U10") (pin "13") (pinfunction "RIN1_13") (pintype "input"))
    )
    (net (code "44") (name "/serial-in_uC") (class "Default")
      (node (ref "U10") (pin "12") (pinfunction "ROUT1_12") (pintype "output"))
      (node (ref "U4") (pin "43") (pinfunction "PA10_43") (pintype "passive"))
    )
    (net (code "45") (name "/serial-out") (class "Default")
      (node (ref "R2") (pin "2") (pinfunction "2_2") (pintype "passive"))
      (node (ref "U10") (pin "14") (pinfunction "DOUT1_14") (pintype "output"))
    )
    (net (code "46") (name "/serial-out_uC") (class "Default")
      (node (ref "U10") (pin "11") (pinfunction "DIN1_11") (pintype "input"))
      (node (ref "U4") (pin "42") (pinfunction "PA9_42") (pintype "passive"))
    )
    (net (code "47") (name "/sppluse") (class "Default")
      (node (ref "R14") (pin "2") (pinfunction "2_2") (pintype "passive"))
      (node (ref "U4") (pin "57") (pinfunction "PB5_57") (pintype "passive"))
    )
    (net (code "48") (name "/threnable") (class "Default")
      (node (ref "D9") (pin "2") (pinfunction "2_2") (pintype "passive"))
      (node (ref "R8") (pin "2") (pinfunction "2_2") (pintype "passive"))
      (node (ref "U4") (pin "25") (pinfunction "PC5_25") (pintype "passive"))
    )
    (net (code "49") (name "/throttle") (class "Default")
      (node (ref "C21") (pin "1") (pinfunction "1_1") (pintype "passive"))
      (node (ref "D7") (pin "1") (pinfunction "1_1") (pintype "passive"))
      (node (ref "R26") (pin "2") (pinfunction "2_2") (pintype "passive"))
      (node (ref "U7") (pin "3") (pinfunction "+_3") (pintype "passive"))
    )
    (net (code "50") (name "/throttle_uC") (class "Default")
      (node (ref "C20") (pin "1") (pinfunction "1_1") (pintype "passive"))
      (node (ref "R21") (pin "2") (pinfunction "2_2") (pintype "passive"))
      (node (ref "R22") (pin "2") (pinfunction "2_2") (pintype "passive"))
      (node (ref "U4") (pin "21") (pinfunction "PA5_21") (pintype "passive"))
    )
    (net (code "51") (name "GND") (class "Default")
      (node (ref "C1") (pin "2") (pinfunction "2_2") (pintype "passive"))
      (node (ref "C10") (pin "2") (pinfunction "2_2") (pintype "passive"))
      (node (ref "C11") (pin "2") (pinfunction "2_2") (pintype "passive"))
      (node (ref "C12") (pin "2") (pinfunction "2_2") (pintype "passive"))
      (node (ref "C13") (pin "2") (pinfunction "2_2") (pintype "passive"))
      (node (ref "C14") (pin "2") (pinfunction "2_2") (pintype "passive"))
      (node (ref "C15") (pin "1") (pinfunction "1_1") (pintype "passive"))
      (node (ref "C16") (pin "2") (pinfunction "2_2") (pintype "passive"))
      (node (ref "C18") (pin "1") (pinfunction "1_1") (pintype "passive"))
      (node (ref "C19") (pin "2") (pinfunction "2_2") (pintype "passive"))
      (node (ref "C2") (pin "2") (pinfunction "2_2") (pintype "passive"))
      (node (ref "C20") (pin "2") (pinfunction "2_2") (pintype "passive"))
      (node (ref "C21") (pin "2") (pinfunction "2_2") (pintype "passive"))
      (node (ref "C22") (pin "1") (pinfunction "1_1") (pintype "passive"))
      (node (ref "C23") (pin "1") (pinfunction "1_1") (pintype "passive"))
      (node (ref "C24") (pin "2") (pinfunction "2_2") (pintype "passive"))
      (node (ref "C25") (pin "2") (pinfunction "2_2") (pintype "passive"))
      (node (ref "C28") (pin "2") (pinfunction "2_2") (pintype "passive"))
      (node (ref "C29") (pin "2") (pinfunction "2_2") (pintype "passive"))
      (node (ref "C3") (pin "2") (pinfunction "2_2") (pintype "passive"))
      (node (ref "C31") (pin "2") (pinfunction "2_2") (pintype "passive"))
      (node (ref "C4") (pin "2") (pinfunction "2_2") (pintype "passive"))
      (node (ref "C5") (pin "2") (pinfunction "2_2") (pintype "passive"))
      (node (ref "C6") (pin "2") (pinfunction "2_2") (pintype "passive"))
      (node (ref "C7") (pin "2") (pinfunction "2_2") (pintype "passive"))
      (node (ref "C8") (pin "1") (pinfunction "1_1") (pintype "passive"))
      (node (ref "C9") (pin "1") (pinfunction "1_1") (pintype "passive"))
      (node (ref "D10") (pin "3") (pinfunction "3_3") (pintype "passive"))
      (node (ref "D13") (pin "3") (pinfunction "3_3") (pintype "passive"))
      (node (ref "D6") (pin "3") (pinfunction "3_3") (pintype "passive"))
      (node (ref "D7") (pin "3") (pinfunction "3_3") (pintype "passive"))
      (node (ref "D8") (pin "3") (pinfunction "3_3") (pintype "passive"))
      (node (ref "D9") (pin "3") (pinfunction "3_3") (pintype "passive"))
      (node (ref "J1") (pin "10") (pinfunction "10_10") (pintype "passive"))
      (node (ref "J1") (pin "8") (pinfunction "8_8") (pintype "passive"))
      (node (ref "J1") (pin "9") (pinfunction "9_9") (pintype "passive"))
      (node (ref "J2") (pin "10") (pinfunction "10_10") (pintype "passive"))
      (node (ref "J2") (pin "8") (pinfunction "8_8") (pintype "passive"))
      (node (ref "J2") (pin "9") (pinfunction "9_9") (pintype "passive"))
      (node (ref "J3") (pin "10") (pinfunction "10_10") (pintype "passive"))
      (node (ref "J3") (pin "14") (pinfunction "14_14") (pintype "passive"))
      (node (ref "J3") (pin "15") (pinfunction "15_15") (pintype "passive"))
      (node (ref "J3") (pin "16") (pinfunction "16_16") (pintype "passive"))
      (node (ref "J3") (pin "17") (pinfunction "17_17") (pintype "passive"))
      (node (ref "J3") (pin "18") (pinfunction "18_18") (pintype "passive"))
      (node (ref "J3") (pin "24") (pinfunction "24_24") (pintype "passive"))
      (node (ref "J4") (pin "3") (pinfunction "GND_3") (pintype "passive"))
      (node (ref "J4") (pin "5") (pinfunction "GND_5") (pintype "passive"))
      (node (ref "J4") (pin "9") (pinfunction "GNDDetect_9") (pintype "passive"))
      (node (ref "J5") (pin "3") (pinfunction "3_3") (pintype "passive"))
      (node (ref "J6") (pin "GND") (pinfunction "GND_GND") (pintype "passive"))
      (node (ref "NJ1") (pin "1") (pinfunction "GND_1") (pintype "passive"))
      (node (ref "NJ2") (pin "1") (pinfunction "GND_1") (pintype "passive"))
      (node (ref "Q1") (pin "2") (pinfunction "SOURCE_2") (pintype "passive"))
      (node (ref "Q3") (pin "2") (pinfunction "SOURCE_2") (pintype "passive"))
      (node (ref "R1") (pin "1") (pinfunction "1_1") (pintype "passive"))
      (node (ref "R10") (pin "2") (pinfunction "2_2") (pintype "passive"))
      (node (ref "R11") (pin "2") (pinfunction "2_2") (pintype "passive"))
      (node (ref "R12") (pin "2") (pinfunction "2_2") (pintype "passive"))
      (node (ref "R13") (pin "2") (pinfunction "2_2") (pintype "passive"))
      (node (ref "R22") (pin "1") (pinfunction "1_1") (pintype "passive"))
      (node (ref "R27") (pin "1") (pinfunction "1_1") (pintype "passive"))
      (node (ref "R3") (pin "2") (pinfunction "2_2") (pintype "passive"))
      (node (ref "R31") (pin "1") (pinfunction "1_1") (pintype "passive"))
      (node (ref "R32") (pin "1") (pinfunction "1_1") (pintype "passive"))
      (node (ref "R33") (pin "1") (pinfunction "1_1") (pintype "passive"))
      (node (ref "R35") (pin "1") (pinfunction "1_1") (pintype "passive"))
      (node (ref "R36") (pin "1") (pinfunction "1_1") (pintype "passive"))
      (node (ref "R37") (pin "2") (pinfunction "2_2") (pintype "passive"))
      (node (ref "R5") (pin "1") (pinfunction "1_1") (pintype "passive"))
      (node (ref "S1") (pin "2") (pinfunction "2_2") (pintype "passive"))
      (node (ref "S2") (pin "2") (pinfunction "2_2") (pintype "passive"))
      (node (ref "SWM2") (pin "2") (pinfunction "2_2") (pintype "passive"))
      (node (ref "U1") (pin "2") (pinfunction "GND_2") (pintype "passive"))
      (node (ref "U1") (pin "5") (pinfunction "LBK_5") (pintype "passive"))
      (node (ref "U10") (pin "15") (pinfunction "GND_15") (pintype "passive"))
      (node (ref "U2") (pin "2") (pinfunction "GND_2") (pintype "passive"))
      (node (ref "U2") (pin "5") (pinfunction "LBK_5") (pintype "passive"))
      (node (ref "U3") (pin "2") (pinfunction "GND_2") (pintype "passive"))
      (node (ref "U4") (pin "12") (pinfunction "VSSA_12") (pintype "passive"))
      (node (ref "U4") (pin "18") (pinfunction "VSS_18") (pintype "passive"))
      (node (ref "U4") (pin "63") (pinfunction "VSS_63") (pintype "passive"))
      (node (ref "U5") (pin "4") (pinfunction "VSS_4") (pintype "passive"))
      (node (ref "U5") (pin "7") (pinfunction "WP_7") (pintype "passive"))
      (node (ref "U6") (pin "2") (pinfunction "GND_2") (pintype "passive"))
      (node (ref "U6") (pin "4") (pinfunction "GND_4") (pintype "passive"))
      (node (ref "U7") (pin "4") (pinfunction "V-_4") (pintype "passive"))
      (node (ref "U8") (pin "2") (pinfunction "GND_2") (pintype "passive"))
      (node (ref "U8") (pin "3") (pinfunction "EN_3") (pintype "passive"))
    )
    (net (code "52") (name "Net-(C10-Pad1)") (class "Default")
      (node (ref "C10") (pin "1") (pinfunction "1_1") (pintype "passive"))
      (node (ref "R9") (pin "2") (pinfunction "2_2") (pintype "passive"))
    )
    (net (code "53") (name "Net-(D2-Cathode)") (class "Default")
      (node (ref "D2") (pin "K") (pinfunction "Cathode_K") (pintype "passive"))
      (node (ref "R10") (pin "1") (pinfunction "1_1") (pintype "passive"))
    )
    (net (code "54") (name "Net-(D3-Cathode)") (class "Default")
      (node (ref "D3") (pin "K") (pinfunction "Cathode_K") (pintype "passive"))
      (node (ref "R11") (pin "1") (pinfunction "1_1") (pintype "passive"))
    )
    (net (code "55") (name "Net-(D4-Cathode)") (class "Default")
      (node (ref "D4") (pin "K") (pinfunction "Cathode_K") (pintype "passive"))
      (node (ref "R12") (pin "1") (pinfunction "1_1") (pintype "passive"))
    )
    (net (code "56") (name "Net-(D5-Cathode)") (class "Default")
      (node (ref "D5") (pin "K") (pinfunction "Cathode_K") (pintype "passive"))
      (node (ref "R13") (pin "1") (pinfunction "1_1") (pintype "passive"))
    )
    (net (code "57") (name "Net-(J3-Pad1)") (class "Default")
      (node (ref "J3") (pin "1") (pinfunction "1_1") (pintype "passive"))
      (node (ref "X2") (pin "2") (pinfunction "2_2") (pintype "passive"))
    )
    (net (code "58") (name "Net-(J3-Pad2)") (class "Default")
      (node (ref "J3") (pin "2") (pinfunction "2_2") (pintype "passive"))
      (node (ref "X3") (pin "2") (pinfunction "2_2") (pintype "passive"))
    )
    (net (code "59") (name "Net-(J3-Pad3)") (class "Default")
      (node (ref "J3") (pin "3") (pinfunction "3_3") (pintype "passive"))
      (node (ref "X4") (pin "2") (pinfunction "2_2") (pintype "passive"))
    )
    (net (code "60") (name "Net-(J3-Pad4)") (class "Default")
      (node (ref "J3") (pin "4") (pinfunction "4_4") (pintype "passive"))
      (node (ref "X5") (pin "2") (pinfunction "2_2") (pintype "passive"))
    )
    (net (code "61") (name "Net-(J3-Pad5)") (class "Default")
      (node (ref "J3") (pin "5") (pinfunction "5_5") (pintype "passive"))
      (node (ref "X6") (pin "2") (pinfunction "2_2") (pintype "passive"))
    )
    (net (code "62") (name "Net-(J3-Pad6)") (class "Default")
      (node (ref "J3") (pin "6") (pinfunction "6_6") (pintype "passive"))
      (node (ref "S2") (pin "4") (pinfunction "4_4") (pintype "passive"))
    )
    (net (code "63") (name "Net-(J3-Pad11)") (class "Default")
      (node (ref "J3") (pin "11") (pinfunction "11_11") (pintype "passive"))
      (node (ref "X10") (pin "2") (pinfunction "2_2") (pintype "passive"))
    )
    (net (code "64") (name "Net-(J3-Pad19)") (class "Default")
      (node (ref "J3") (pin "19") (pinfunction "19_19") (pintype "passive"))
      (node (ref "S2") (pin "3") (pinfunction "3_3") (pintype "passive"))
    )
    (net (code "65") (name "Net-(J3-Pad22)") (class "Default")
      (node (ref "J3") (pin "22") (pinfunction "22_22") (pintype "passive"))
      (node (ref "X8") (pin "2") (pinfunction "2_2") (pintype "passive"))
    )
    (net (code "66") (name "Net-(J3-Pad23)") (class "Default")
      (node (ref "J3") (pin "23") (pinfunction "23_23") (pintype "passive"))
      (node (ref "J3") (pin "9") (pinfunction "9_9") (pintype "passive"))
      (node (ref "X7") (pin "2") (pinfunction "2_2") (pintype "passive"))
    )
    (net (code "67") (name "Net-(J6-PaduRX)") (class "Default")
      (node (ref "J6") (pin "uRX") (pinfunction "uRX_uRX") (pintype "passive"))
      (node (ref "R25") (pin "1") (pinfunction "1_1") (pintype "passive"))
    )
    (net (code "68") (name "Net-(J6-PaduTX)") (class "Default")
      (node (ref "J6") (pin "uTX") (pinfunction "uTX_uTX") (pintype "passive"))
      (node (ref "R24") (pin "1") (pinfunction "1_1") (pintype "passive"))
    )
    (net (code "69") (name "Net-(NJ1-KILL)") (class "Default")
      (node (ref "NJ1") (pin "4") (pinfunction "KILL_4") (pintype "passive"))
      (node (ref "NJ2") (pin "4") (pinfunction "KILL_4") (pintype "passive"))
    )
    (net (code "70") (name "Net-(NJ1-SHIELD)") (class "Default")
      (node (ref "J5") (pin "1") (pinfunction "1_1") (pintype "passive"))
      (node (ref "NJ1") (pin "6") (pinfunction "SHIELD_6") (pintype "passive"))
      (node (ref "NJ2") (pin "6") (pinfunction "SHIELD_6") (pintype "passive"))
    )
    (net (code "71") (name "Net-(R2-Pad1)") (class "Default")
      (node (ref "R2") (pin "1") (pinfunction "1_1") (pintype "passive"))
      (node (ref "X2") (pin "1") (pinfunction "1_1") (pintype "passive"))
    )
    (net (code "72") (name "Net-(R4-Pad1)") (class "Default")
      (node (ref "R4") (pin "1") (pinfunction "1_1") (pintype "passive"))
      (node (ref "X3") (pin "1") (pinfunction "1_1") (pintype "passive"))
    )
    (net (code "73") (name "Net-(R6-Pad1)") (class "Default")
      (node (ref "R6") (pin "1") (pinfunction "1_1") (pintype "passive"))
      (node (ref "X4") (pin "1") (pinfunction "1_1") (pintype "passive"))
    )
    (net (code "74") (name "Net-(R8-Pad1)") (class "Default")
      (node (ref "R8") (pin "1") (pinfunction "1_1") (pintype "passive"))
      (node (ref "X5") (pin "1") (pinfunction "1_1") (pintype "passive"))
    )
    (net (code "75") (name "Net-(R14-Pad1)") (class "Default")
      (node (ref "R14") (pin "1") (pinfunction "1_1") (pintype "passive"))
      (node (ref "S2") (pin "1") (pinfunction "1_1") (pintype "passive"))
    )
    (net (code "76") (name "Net-(R15-Pad1)") (class "Default")
      (node (ref "R15") (pin "1") (pinfunction "1_1") (pintype "passive"))
      (node (ref "X6") (pin "1") (pinfunction "1_1") (pintype "passive"))
    )
    (net (code "77") (name "Net-(R19-Pad1)") (class "Default")
      (node (ref "R19") (pin "1") (pinfunction "1_1") (pintype "passive"))
      (node (ref "S1") (pin "3") (pinfunction "3_3") (pintype "passive"))
    )
    (net (code "78") (name "Net-(R20-Pad1)") (class "Default")
      (node (ref "R20") (pin "1") (pinfunction "1_1") (pintype "passive"))
      (node (ref "S1") (pin "1") (pinfunction "1_1") (pintype "passive"))
    )
    (net (code "79") (name "Net-(R23-Pad1)") (class "Default")
      (node (ref "R23") (pin "1") (pinfunction "1_1") (pintype "passive"))
      (node (ref "X7") (pin "1") (pinfunction "1_1") (pintype "passive"))
    )
    (net (code "80") (name "Net-(R26-Pad1)") (class "Default")
      (node (ref "R26") (pin "1") (pinfunction "1_1") (pintype "passive"))
      (node (ref "R31") (pin "2") (pinfunction "2_2") (pintype "passive"))
      (node (ref "X8") (pin "1") (pinfunction "1_1") (pintype "passive"))
    )
    (net (code "81") (name "Net-(R29-Pad1)") (class "Default")
      (node (ref "R29") (pin "1") (pinfunction "1_1") (pintype "passive"))
      (node (ref "R33") (pin "2") (pinfunction "2_2") (pintype "passive"))
      (node (ref "X10") (pin "1") (pinfunction "1_1") (pintype "passive"))
    )
    (net (code "82") (name "Net-(U1-RS)") (class "Default")
      (node (ref "R1") (pin "2") (pinfunction "2_2") (pintype "passive"))
      (node (ref "U1") (pin "8") (pinfunction "RS_8") (pintype "passive"))
    )
    (net (code "83") (name "Net-(U2-RS)") (class "Default")
      (node (ref "R5") (pin "2") (pinfunction "2_2") (pintype "passive"))
      (node (ref "U2") (pin "8") (pinfunction "RS_8") (pintype "passive"))
    )
    (net (code "84") (name "Net-(U3-VCC)") (class "Default")
      (node (ref "D6") (pin "1") (pinfunction "1_1") (pintype "passive"))
      (node (ref "D6") (pin "2") (pinfunction "2_2") (pintype "passive"))
      (node (ref "F1") (pin "2") (pinfunction "2_2") (pintype "passive"))
      (node (ref "R9") (pin "1") (pinfunction "1_1") (pintype "passive"))
      (node (ref "U3") (pin "1") (pinfunction "VCC_1") (pintype "passive"))
    )
    (net (code "85") (name "Net-(U7A--)") (class "Default")
      (node (ref "R21") (pin "1") (pinfunction "1_1") (pintype "passive"))
      (node (ref "U7") (pin "1") (pinfunction "Vo_1") (pintype "passive"))
      (node (ref "U7") (pin "2") (pinfunction "-_2") (pintype "passive"))
    )
    (net (code "86") (name "Net-(U7B--)") (class "Default")
      (node (ref "R30") (pin "1") (pinfunction "1_1") (pintype "passive"))
      (node (ref "U7") (pin "6") (pinfunction "-_6") (pintype "passive"))
      (node (ref "U7") (pin "7") (pinfunction "Vo_7") (pintype "passive"))
    )
    (net (code "87") (name "Net-(U8-ILIM*)") (class "Default")
      (node (ref "R27") (pin "2") (pinfunction "2_2") (pintype "passive"))
      (node (ref "U8") (pin "5") (pinfunction "ILIM*_5") (pintype "passive"))
    )
    (net (code "88") (name "Net-(U10-C1+)") (class "Default")
      (node (ref "C30") (pin "2") (pinfunction "2_2") (pintype "passive"))
      (node (ref "U10") (pin "1") (pinfunction "C1+_1") (pintype "passive"))
    )
    (net (code "89") (name "Net-(U10-C1-)") (class "Default")
      (node (ref "C30") (pin "1") (pinfunction "1_1") (pintype "passive"))
      (node (ref "U10") (pin "3") (pinfunction "C1-_3") (pintype "passive"))
    )
    (net (code "90") (name "Net-(U10-C2+)") (class "Default")
      (node (ref "C32") (pin "2") (pinfunction "2_2") (pintype "passive"))
      (node (ref "U10") (pin "4") (pinfunction "C2+_4") (pintype "passive"))
    )
    (net (code "91") (name "Net-(U10-C2-)") (class "Default")
      (node (ref "C32") (pin "1") (pinfunction "1_1") (pintype "passive"))
      (node (ref "U10") (pin "5") (pinfunction "C2-_5") (pintype "passive"))
    )
    (net (code "92") (name "Net-(U10-V+)") (class "Default")
      (node (ref "C29") (pin "1") (pinfunction "1_1") (pintype "passive"))
      (node (ref "U10") (pin "2") (pinfunction "V+_2") (pintype "passive"))
    )
    (net (code "93") (name "Net-(U10-V-)") (class "Default")
      (node (ref "C31") (pin "1") (pinfunction "1_1") (pintype "passive"))
      (node (ref "U10") (pin "6") (pinfunction "V-_6") (pintype "passive"))
    )
    (net (code "94") (name "unconnected-(J3-Pad12)") (class "Default")
      (node (ref "J3") (pin "12") (pinfunction "12_12") (pintype "passive+no_connect"))
    )
    (net (code "95") (name "unconnected-(J3-Pad13)") (class "Default")
      (node (ref "J3") (pin "13") (pinfunction "13_13") (pintype "passive+no_connect"))
    )
    (net (code "96") (name "unconnected-(J3-Pad20)") (class "Default")
      (node (ref "J3") (pin "20") (pinfunction "20_20") (pintype "passive+no_connect"))
    )
    (net (code "97") (name "unconnected-(J3-Pad21)") (class "Default")
      (node (ref "J3") (pin "21") (pinfunction "21_21") (pintype "passive+no_connect"))
    )
    (net (code "98") (name "unconnected-(J3-Pad25)") (class "Default")
      (node (ref "J3") (pin "25") (pinfunction "25_25") (pintype "passive+no_connect"))
    )
    (net (code "99") (name "unconnected-(U4-PA0_WKUP-Pad14)") (class "Default")
      (node (ref "U4") (pin "14") (pinfunction "PA0_WKUP_14") (pintype "passive"))
    )
    (net (code "100") (name "unconnected-(U4-PA1-Pad15)") (class "Default")
      (node (ref "U4") (pin "15") (pinfunction "PA1_15") (pintype "passive"))
    )
    (net (code "101") (name "unconnected-(U4-PA2-Pad16)") (class "Default")
      (node (ref "U4") (pin "16") (pinfunction "PA2_16") (pintype "passive"))
    )
    (net (code "102") (name "unconnected-(U4-PA3-Pad17)") (class "Default")
      (node (ref "U4") (pin "17") (pinfunction "PA3_17") (pintype "passive"))
    )
    (net (code "103") (name "unconnected-(U4-PA4-Pad20)") (class "Default")
      (node (ref "U4") (pin "20") (pinfunction "PA4_20") (pintype "passive"))
    )
    (net (code "104") (name "unconnected-(U4-PA8-Pad41)") (class "Default")
      (node (ref "U4") (pin "41") (pinfunction "PA8_41") (pintype "passive"))
    )
    (net (code "105") (name "unconnected-(U4-PA11-Pad44)") (class "Default")
      (node (ref "U4") (pin "44") (pinfunction "PA11_44") (pintype "passive"))
    )
    (net (code "106") (name "unconnected-(U4-PA12-Pad45)") (class "Default")
      (node (ref "U4") (pin "45") (pinfunction "PA12_45") (pintype "passive"))
    )
    (net (code "107") (name "unconnected-(U4-PB14-Pad35)") (class "Default")
      (node (ref "U4") (pin "35") (pinfunction "PB14_35") (pintype "passive"))
    )
    (net (code "108") (name "unconnected-(U4-PB15-Pad36)") (class "Default")
      (node (ref "U4") (pin "36") (pinfunction "PB15_36") (pintype "passive"))
    )
    (net (code "109") (name "unconnected-(U4-PC1-Pad9)") (class "Default")
      (node (ref "U4") (pin "9") (pinfunction "PC1_9") (pintype "passive"))
    )
    (net (code "110") (name "unconnected-(U4-PC2-Pad10)") (class "Default")
      (node (ref "U4") (pin "10") (pinfunction "PC2_10") (pintype "passive"))
    )
    (net (code "111") (name "unconnected-(U4-PC3-Pad11)") (class "Default")
      (node (ref "U4") (pin "11") (pinfunction "PC3_11") (pintype "passive"))
    )
    (net (code "112") (name "unconnected-(U4-PC6-Pad37)") (class "Default")
      (node (ref "U4") (pin "37") (pinfunction "PC6_37") (pintype "passive"))
    )
    (net (code "113") (name "unconnected-(U4-PC7-Pad38)") (class "Default")
      (node (ref "U4") (pin "38") (pinfunction "PC7_38") (pintype "passive"))
    )
    (net (code "114") (name "unconnected-(U4-PC8-Pad39)") (class "Default")
      (node (ref "U4") (pin "39") (pinfunction "PC8_39") (pintype "passive"))
    )
    (net (code "115") (name "unconnected-(U4-PC9-Pad40)") (class "Default")
      (node (ref "U4") (pin "40") (pinfunction "PC9_40") (pintype "passive"))
    )
    (net (code "116") (name "unconnected-(U4-PC10-Pad51)") (class "Default")
      (node (ref "U4") (pin "51") (pinfunction "PC10_51") (pintype "passive"))
    )
    (net (code "117") (name "unconnected-(U4-PC11-Pad52)") (class "Default")
      (node (ref "U4") (pin "52") (pinfunction "PC11_52") (pintype "passive"))
    )
    (net (code "118") (name "unconnected-(U4-PC12-Pad53)") (class "Default")
      (node (ref "U4") (pin "53") (pinfunction "PC12_53") (pintype "passive"))
    )
    (net (code "119") (name "unconnected-(U5-NC-Pad1)") (class "Default")
      (node (ref "U5") (pin "1") (pinfunction "NC_1") (pintype "passive"))
    )
    (net (code "120") (name "unconnected-(U5-NC-Pad2)") (class "Default")
      (node (ref "U5") (pin "2") (pinfunction "NC_2") (pintype "passive"))
    )
    (net (code "121") (name "unconnected-(U5-NC-Pad3)") (class "Default")
      (node (ref "U5") (pin "3") (pinfunction "NC_3") (pintype "passive"))
    )
    (net (code "122") (name "unconnected-(U10-DIN2-Pad10)") (class "Default")
      (node (ref "U10") (pin "10") (pinfunction "DIN2_10") (pintype "input"))
    )
    (net (code "123") (name "unconnected-(U10-DOUT2-Pad7)") (class "Default")
      (node (ref "U10") (pin "7") (pinfunction "DOUT2_7") (pintype "output"))
    )
    (net (code "124") (name "unconnected-(U10-RIN2-Pad8)") (class "Default")
      (node (ref "U10") (pin "8") (pinfunction "RIN2_8") (pintype "input"))
    )
    (net (code "125") (name "unconnected-(U10-ROUT2-Pad9)") (class "Default")
      (node (ref "U10") (pin "9") (pinfunction "ROUT2_9") (pintype "output"))
    )
  )
)
